# Convertidor.net
KiCad netlist of a schematic drawn in Altium Designer
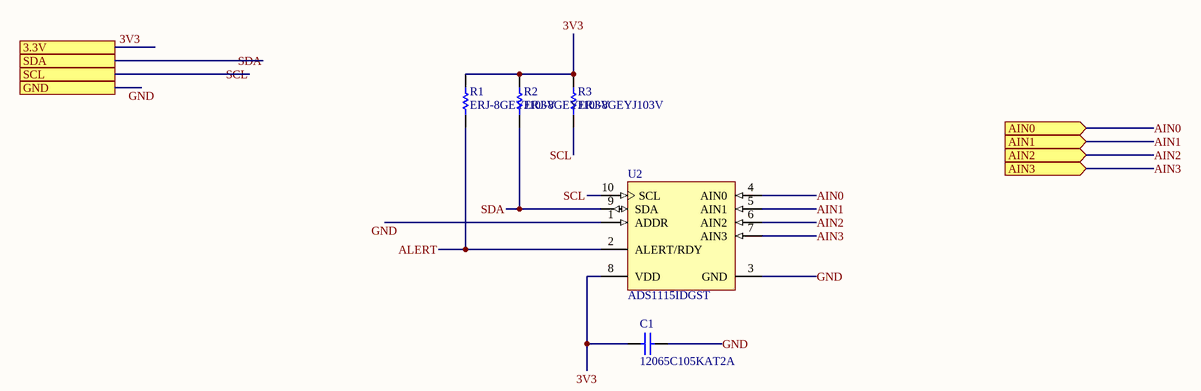
[diagram p0: Convertidor.SchDoc]

(export (version "E")
  (design (tool "Eeschema 10.0.6"))
  (components
    (comp (ref "C1")
      (value "12065C105KAT2A")
      (footprint "CAPC3216X180X50LL20T25")
      (description "Chip Capacitor, 1 uF, +/- 10%, 50 V, -55 to 125 degC, 1206 (3216 Metric), RoHS, Tape and Reel")
      (fields (field (name "MANUFACTURER") "AVX"))
      (libsource (lib "Altium Content Vault") (part "CAP-NP-2"))
    )
    (comp (ref "R1")
      (value "ERJ-8GEYJ103V")
      (footprint "RESC3216X70X50NL05T20")
      (fields (field (name "MANUFACTURER") "Panasonic"))
      (libsource (lib "Altium Content Vault") (part "RES"))
    )
    (comp (ref "R2")
      (value "ERJ-8GEYJ103V")
      (footprint "RESC3216X70X50NL05T20")
      (fields (field (name "MANUFACTURER") "Panasonic"))
      (libsource (lib "Altium Content Vault") (part "RES"))
    )
    (comp (ref "R3")
      (value "ERJ-8GEYJ103V")
      (footprint "RESC3216X70X50NL05T20")
      (fields (field (name "MANUFACTURER") "Panasonic"))
      (libsource (lib "Altium Content Vault") (part "RES"))
    )
    (comp (ref "U2")
      (value "ADS1115IDGST")
      (footprint "TI-DGS10_M")
      (fields (field (name "MANUFACTURER") "Texas Instruments"))
      (libsource (lib "Altium Content Vault") (part "TI-ADS1015_1115-10"))
    )
  )
  (nets
    (net (code "1") (name "/3V3") (class "Default")
      (node (ref "C1") (pin "2") (pinfunction "2_2") (pintype "passive"))
      (node (ref "R1") (pin "2") (pinfunction "2_2") (pintype "passive"))
      (node (ref "R2") (pin "2") (pinfunction "2_2") (pintype "passive"))
      (node (ref "R3") (pin "2") (pinfunction "2_2") (pintype "passive"))
      (node (ref "U2") (pin "8") (pinfunction "VDD_8") (pintype "power_in"))
    )
    (net (code "2") (name "/AIN0") (class "Default")
      (node (ref "U2") (pin "4") (pinfunction "AIN0_4") (pintype "input"))
    )
    (net (code "3") (name "/AIN1") (class "Default")
      (node (ref "U2") (pin "5") (pinfunction "AIN1_5") (pintype "input"))
    )
    (net (code "4") (name "/AIN2") (class "Default")
      (node (ref "U2") (pin "6") (pinfunction "AIN2_6") (pintype "input"))
    )
    (net (code "5") (name "/AIN3") (class "Default")
      (node (ref "U2") (pin "7") (pinfunction "AIN3_7") (pintype "input"))
    )
    (net (code "6") (name "/ALERT") (class "Default")
      (node (ref "R1") (pin "1") (pinfunction "1_1") (pintype "passive"))
      (node (ref "U2") (pin "2") (pinfunction "ALERT/RDY_2") (pintype "open_collector"))
    )
    (net (code "7") (name "/GND") (class "Default")
      (node (ref "C1") (pin "1") (pinfunction "1_1") (pintype "passive"))
      (node (ref "U2") (pin "1") (pinfunction "ADDR_1") (pintype "input"))
      (node (ref "U2") (pin "3") (pinfunction "GND_3") (pintype "power_in"))
    )
    (net (code "8") (name "/SCL") (class "Default")
      (node (ref "R3") (pin "1") (pinfunction "1_1") (pintype "passive"))
      (node (ref "U2") (pin "10") (pinfunction "SCL_10") (pintype "input"))
    )
    (net (code "9") (name "/SDA") (class "Default")
      (node (ref "R2") (pin "1") (pinfunction "1_1") (pintype "passive"))
      (node (ref "U2") (pin "9") (pinfunction "SDA_9") (pintype "bidirectional"))
    )
  )
)
